# PowerSection.net
KiCad netlist of a schematic drawn in EAGLE
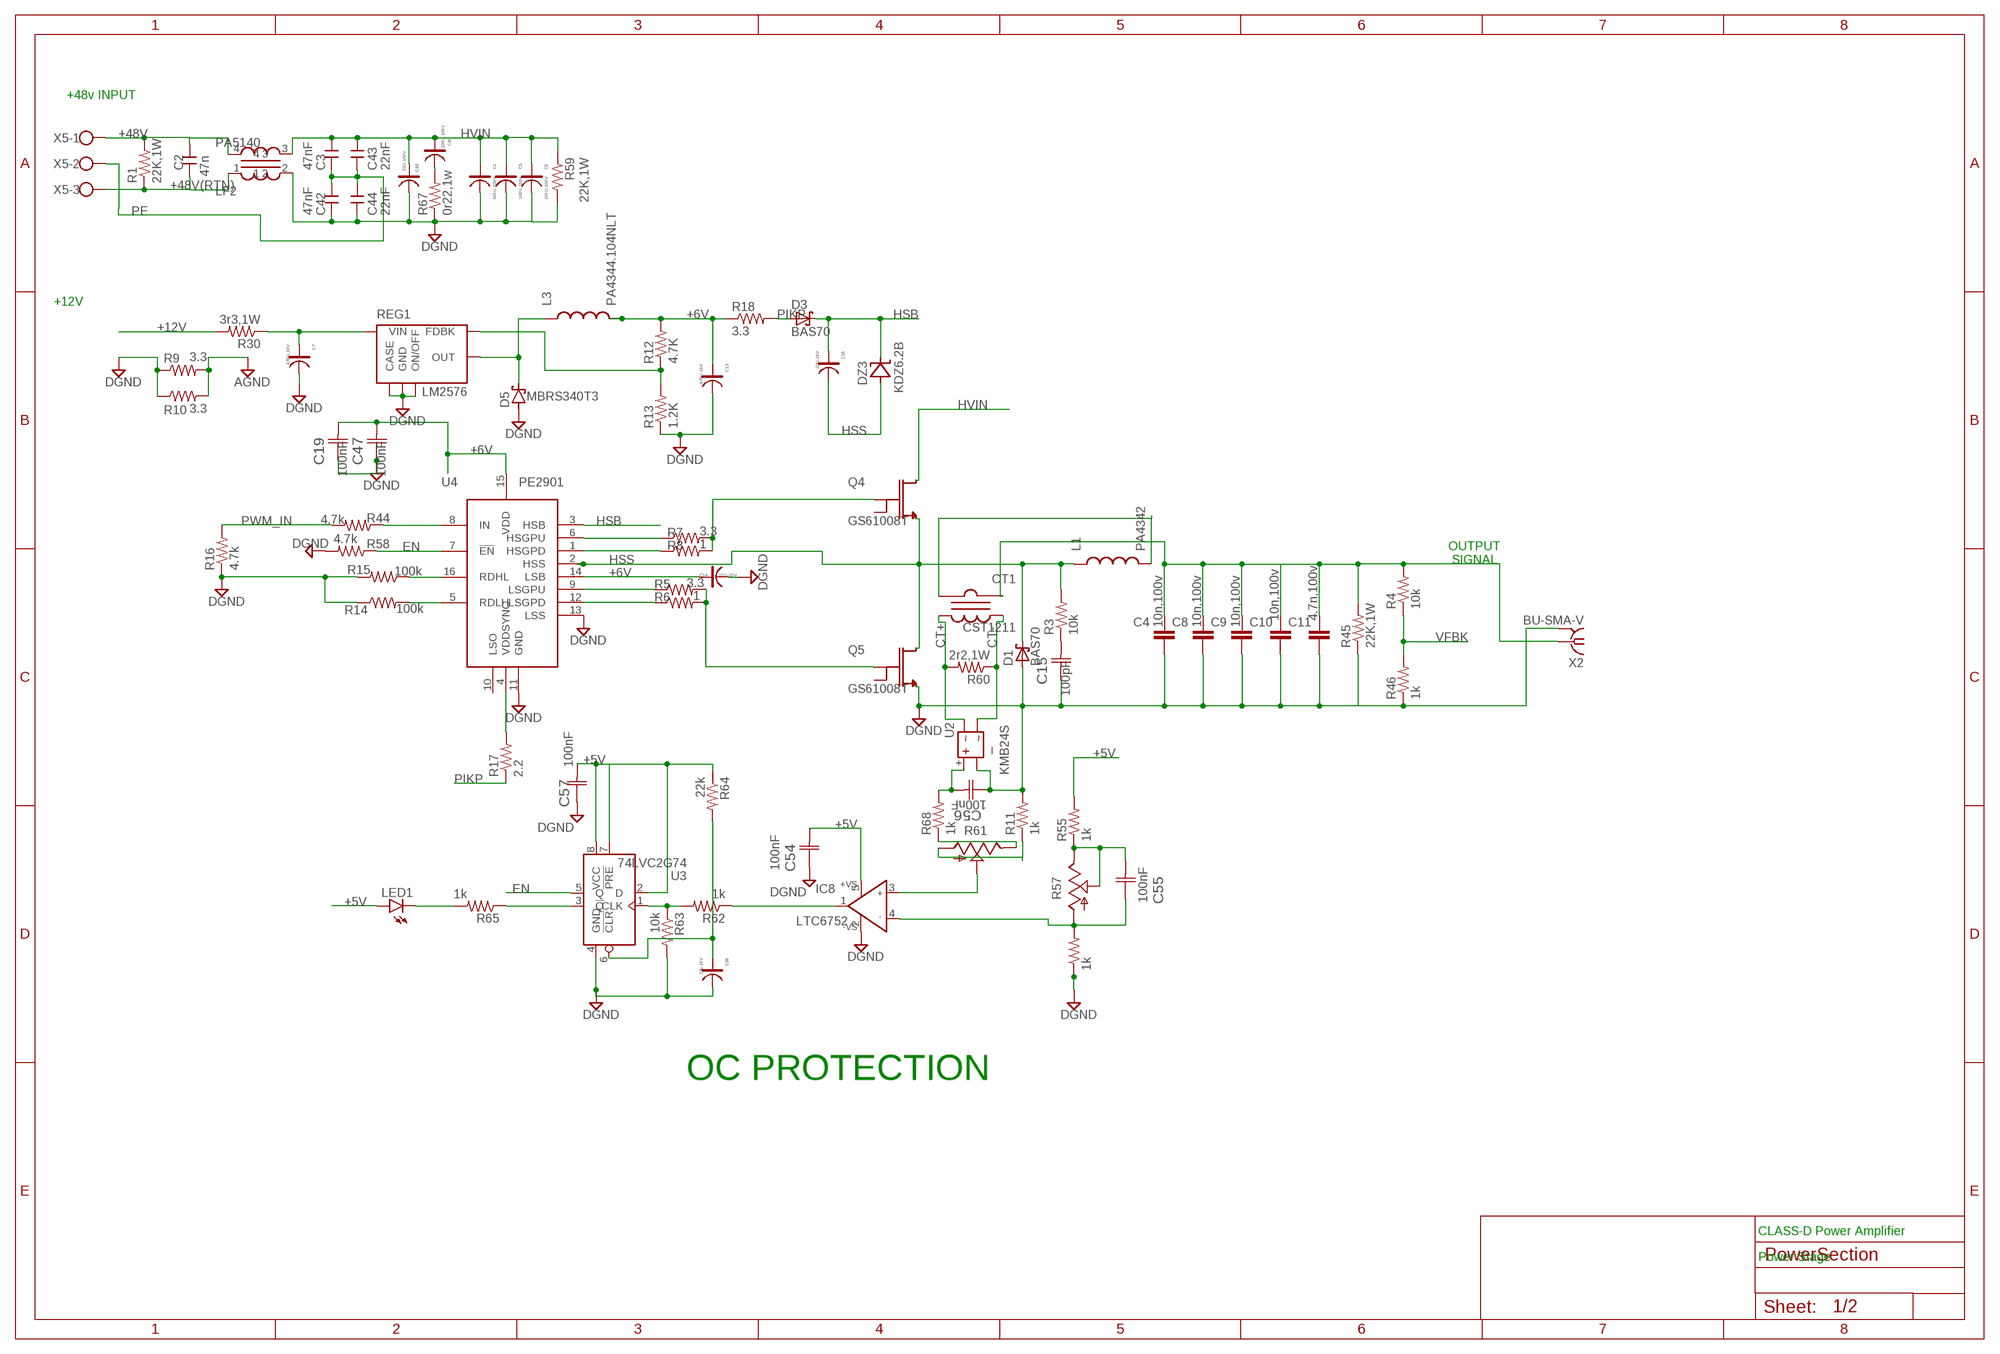
[diagram p0: schematic, sheet 1]
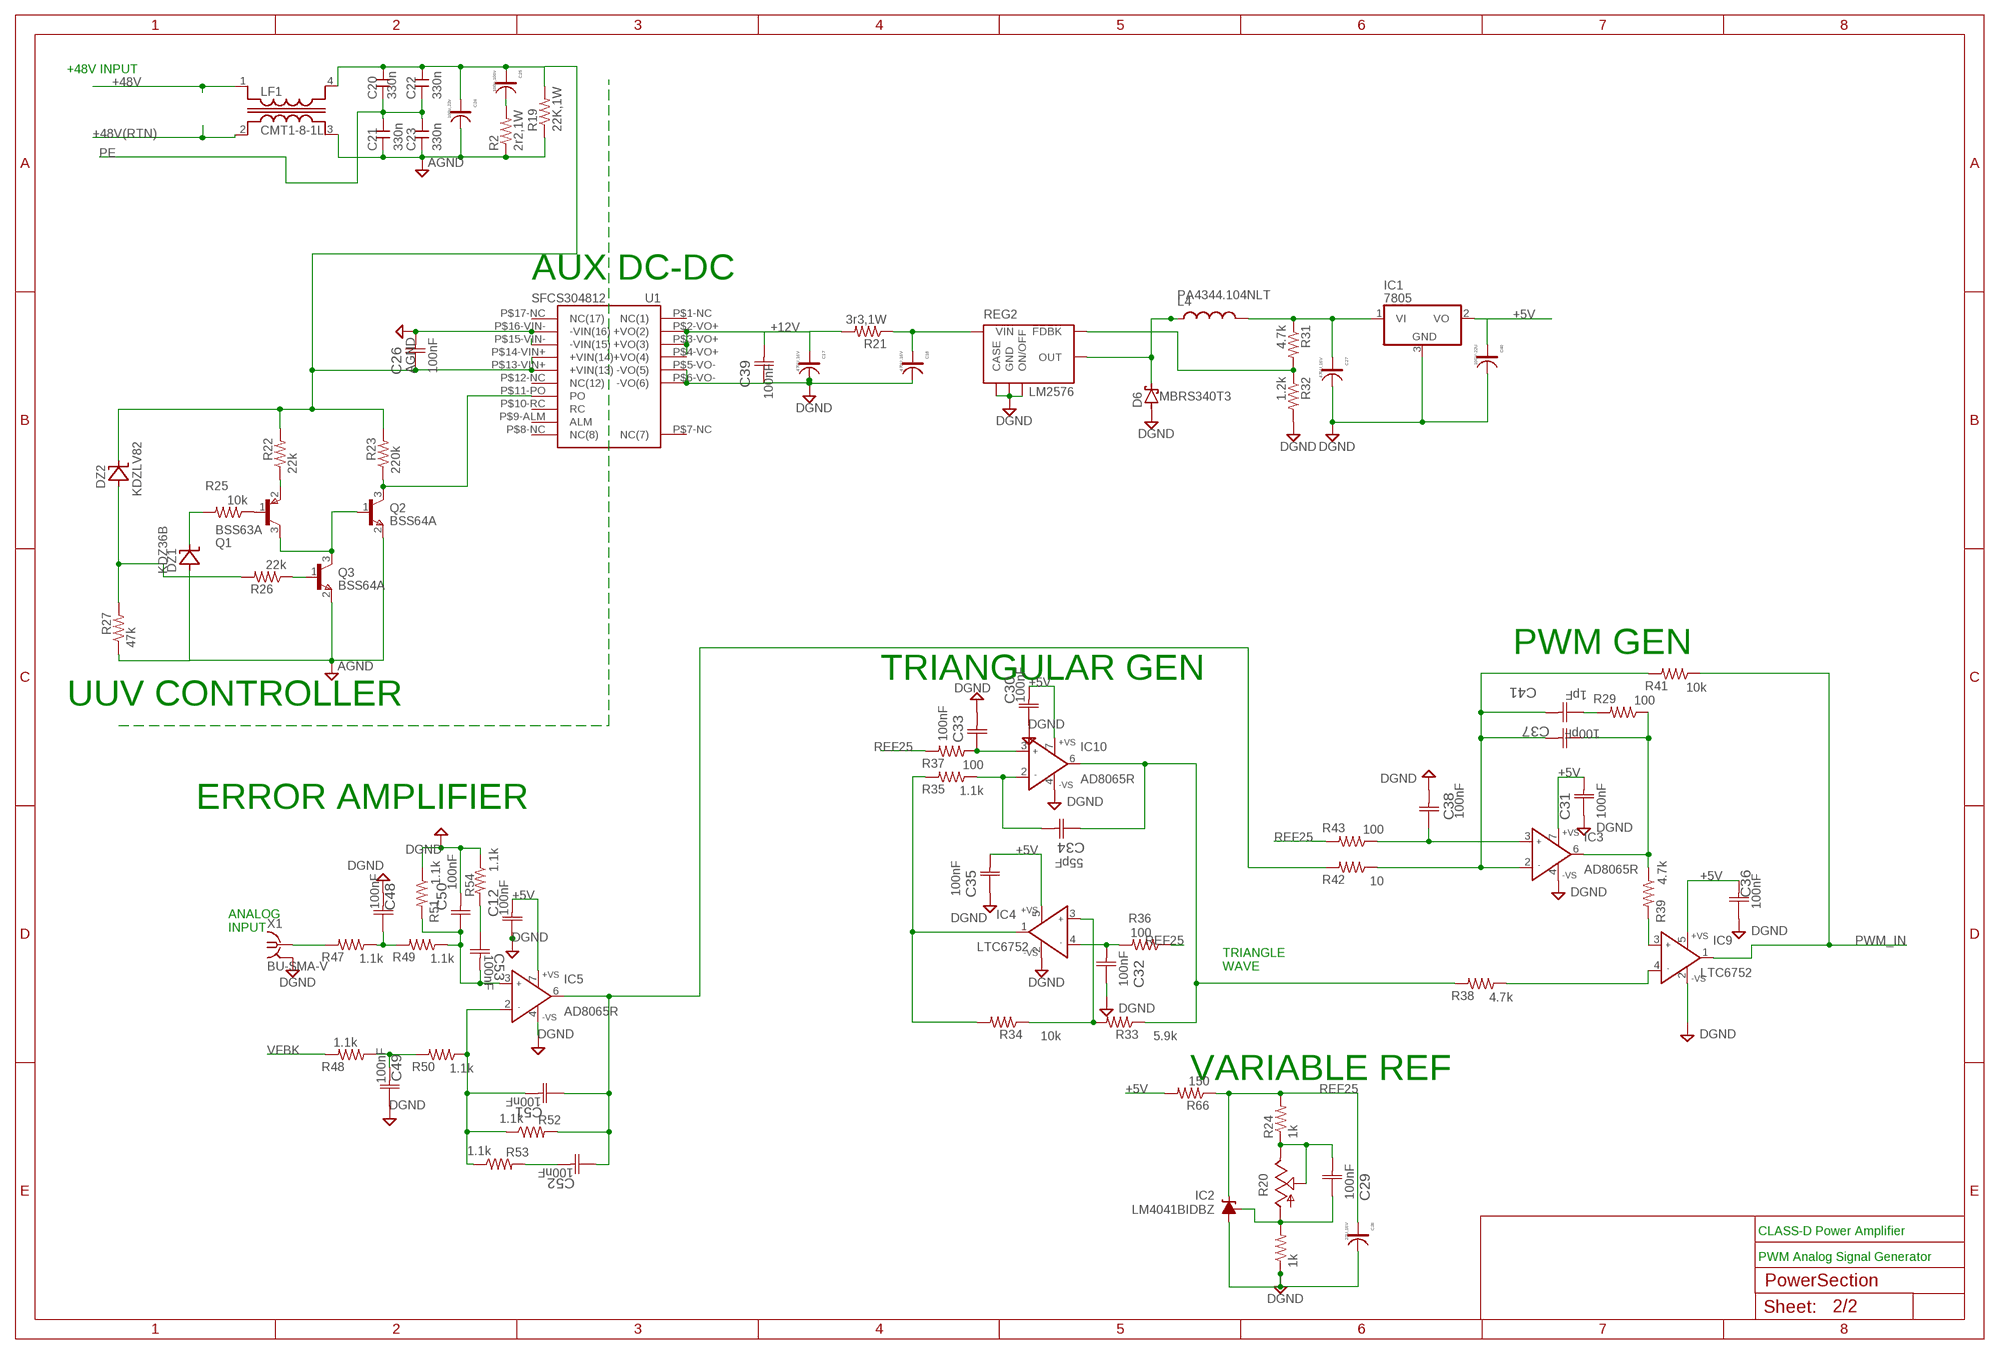
[diagram p1: schematic, sheet 2]

(export (version "E")
  (design (tool "Eeschema 10.0.6"))
  (components
    (comp (ref "C1")
      (value "100U,100V")
      (footprint "eagle-import:CEL-EDH-9R")
      (libsource (lib "eagle-import") (part "C-EDH-100V-100U"))
    )
    (comp (ref "C2")
      (value "47n")
      (footprint "eagle-import:2220")
      (libsource (lib "eagle-import") (part "C"))
    )
    (comp (ref "C3")
      (value "47nF")
      (footprint "eagle-import:2220")
      (libsource (lib "eagle-import") (part "C-SMD-2220"))
    )
    (comp (ref "C4")
      (value "10n,100v")
      (footprint "eagle-import:C2220K")
      (libsource (lib "eagle-import") (part "C-EUC2220K"))
    )
    (comp (ref "C5")
      (value "100U,100v")
      (footprint "eagle-import:CEL-EDH-9R")
      (libsource (lib "eagle-import") (part "C-EDH-100V-100U"))
    )
    (comp (ref "C6")
      (value "100U,100V")
      (footprint "eagle-import:CEL-EDH-9R")
      (libsource (lib "eagle-import") (part "C-EDH-100V-100U"))
    )
    (comp (ref "C7")
      (value "470U,16V")
      (footprint "eagle-import:CEL-EDH-9P")
      (libsource (lib "eagle-import") (part "C-EDH-470U,16V"))
    )
    (comp (ref "C8")
      (value "10n,100v")
      (footprint "eagle-import:C2220K")
      (libsource (lib "eagle-import") (part "C-EUC2220K"))
    )
    (comp (ref "C9")
      (value "10n,100v")
      (footprint "eagle-import:C2220K")
      (libsource (lib "eagle-import") (part "C-EUC2220K"))
    )
    (comp (ref "C10")
      (value "10n,100v")
      (footprint "eagle-import:C2220K")
      (libsource (lib "eagle-import") (part "C-EUC2220K"))
    )
    (comp (ref "C11")
      (value "4.7n,100v")
      (footprint "eagle-import:C2225K")
      (libsource (lib "eagle-import") (part "C-EUC2225K"))
    )
    (comp (ref "C13")
      (value "470U,16V")
      (footprint "eagle-import:CEL-EDH-9P")
      (libsource (lib "eagle-import") (part "C-EDH-470U,16V"))
    )
    (comp (ref "C14")
      (value "10U-16V")
      (footprint "eagle-import:CEL-EDK-9B")
      (libsource (lib "eagle-import") (part "C-EDK-10U-16V"))
    )
    (comp (ref "C15")
      (value "100pF")
      (footprint "eagle-import:CAPC3216X88N")
      (fields (field (name "MPN") "C1206C104K1RACTU") (field (name "TOLERANCE") "±10%"))
      (libsource (lib "eagle-import") (part "C1206C104K1RACTU"))
    )
    (comp (ref "C16")
      (value "22U,16V")
      (footprint "eagle-import:CEL-EDK-9D")
      (libsource (lib "eagle-import") (part "C-EDK-22U-16V"))
    )
    (comp (ref "C19")
      (value "100nF")
      (footprint "eagle-import:CAPC3216X88N")
      (fields (field (name "MPN") "C1206C104K1RACTU") (field (name "TOLERANCE") "±10%"))
      (libsource (lib "eagle-import") (part "C1206C104K1RACTU"))
    )
    (comp (ref "C42")
      (value "47nF")
      (footprint "eagle-import:2220")
      (libsource (lib "eagle-import") (part "C-SMD-2220"))
    )
    (comp (ref "C43")
      (value "22nF")
      (footprint "eagle-import:2220")
      (libsource (lib "eagle-import") (part "C-SMD-2220"))
    )
    (comp (ref "C44")
      (value "22nF")
      (footprint "eagle-import:2220")
      (libsource (lib "eagle-import") (part "C-SMD-2220"))
    )
    (comp (ref "C45")
      (value "22U,100V")
      (footprint "eagle-import:CEL-EDH-9M")
      (libsource (lib "eagle-import") (part "C-EDH-100V-22U"))
    )
    (comp (ref "C46")
      (value "100U,100V")
      (footprint "eagle-import:CEL-EDH-9R")
      (libsource (lib "eagle-import") (part "C-EDH-100V-100U"))
    )
    (comp (ref "C47")
      (value "100nF")
      (footprint "eagle-import:CAPC3216X88N")
      (fields (field (name "MPN") "C1206C104K1RACTU") (field (name "TOLERANCE") "±10%"))
      (libsource (lib "eagle-import") (part "C1206C104K1RACTU"))
    )
    (comp (ref "C54")
      (value "100nF")
      (footprint "eagle-import:CAPC3216X88N")
      (fields (field (name "MPN") "C1206C104K5RACTU") (field (name "TOLERANCE") "±10%"))
      (libsource (lib "eagle-import") (part "C1206C104K5RACTU"))
    )
    (comp (ref "C55")
      (value "100nF")
      (footprint "eagle-import:CAPC3216X88N")
      (fields (field (name "MPN") "C1206C104K5RACTU") (field (name "TOLERANCE") "±10%"))
      (libsource (lib "eagle-import") (part "C1206C104K5RACTU"))
    )
    (comp (ref "C56")
      (value "100nF")
      (footprint "eagle-import:CAPC3216X88N")
      (fields (field (name "MPN") "C1206C104K5RACTU") (field (name "TOLERANCE") "±10%"))
      (libsource (lib "eagle-import") (part "C1206C104K5RACTU"))
    )
    (comp (ref "C57")
      (value "100nF")
      (footprint "eagle-import:CAPC3216X88N")
      (fields (field (name "MPN") "C1206C104K5RACTU") (field (name "TOLERANCE") "±10%"))
      (libsource (lib "eagle-import") (part "C1206C104K5RACTU"))
    )
    (comp (ref "C58")
      (value "22u,16V")
      (footprint "eagle-import:CEL-EDK-9D")
      (libsource (lib "eagle-import") (part "C-EDK-22U-16V"))
    )
    (comp (ref "CT1")
      (value "CST1211")
      (footprint "eagle-import:CST1211")
      (libsource (lib "eagle-import") (part "CST1211"))
    )
    (comp (ref "D1")
      (value "BAS70")
      (footprint "eagle-import:SOT23")
      (libsource (lib "eagle-import") (part "BAS70"))
    )
    (comp (ref "D3")
      (value "BAS70")
      (footprint "eagle-import:SOT23")
      (libsource (lib "eagle-import") (part "BAS70"))
    )
    (comp (ref "D5")
      (value "MBRS340T3")
      (footprint "eagle-import:SMC")
      (libsource (lib "eagle-import") (part "MBRS30T34"))
    )
    (comp (ref "DZ3")
      (value "KDZ6.2B")
      (footprint "eagle-import:SOD123FL")
      (libsource (lib "eagle-import") (part "KDZ36B"))
    )
    (comp (ref "IC8")
      (value "LTC6752")
      (footprint "eagle-import:SOT23-5")
      (fields (field (name "MF") "ALTERA CORPORATION") (field (name "MPN") "AD8065ARTZ-REEL7"))
      (libsource (lib "eagle-import") (part "AD8065RT"))
    )
    (comp (ref "L1")
      (value "PA4342")
      (footprint "eagle-import:PA4342")
      (libsource (lib "eagle-import") (part "PA4342"))
    )
    (comp (ref "L3")
      (value "PA4344.104NLT")
      (footprint "eagle-import:104NLT")
      (libsource (lib "eagle-import") (part "PA4344.104NLT"))
    )
    (comp (ref "LED1")
      (value "LEDCHIPLED_1206")
      (footprint "eagle-import:CHIPLED_1206")
      (libsource (lib "eagle-import") (part "LEDCHIPLED_1206"))
    )
    (comp (ref "LF2")
      (value "PA5140")
      (footprint "eagle-import:PA5140.XXXNL")
      (libsource (lib "eagle-import") (part "PA5140"))
    )
    (comp (ref "Q4")
      (value "GS61008T")
      (footprint "eagle-import:61008T")
      (libsource (lib "eagle-import") (part "GS61008T"))
    )
    (comp (ref "Q5")
      (value "GS61008T")
      (footprint "eagle-import:61008T")
      (libsource (lib "eagle-import") (part "GS61008T"))
    )
    (comp (ref "R1")
      (value "22K,1W")
      (footprint "eagle-import:R2512W")
      (libsource (lib "eagle-import") (part "R-US_R2512W"))
    )
    (comp (ref "R3")
      (value "10k")
      (footprint "eagle-import:R1206")
      (libsource (lib "eagle-import") (part "R-US_R1206"))
    )
    (comp (ref "R4")
      (value "10k")
      (footprint "eagle-import:R1206")
      (libsource (lib "eagle-import") (part "R-US_R1206"))
    )
    (comp (ref "R5")
      (value "3.3")
      (footprint "eagle-import:R1206")
      (libsource (lib "eagle-import") (part "R-US_R1206"))
    )
    (comp (ref "R6")
      (value "1")
      (footprint "eagle-import:R1206")
      (libsource (lib "eagle-import") (part "R-US_R1206"))
    )
    (comp (ref "R7")
      (value "3.3")
      (footprint "eagle-import:R1206")
      (libsource (lib "eagle-import") (part "R-US_R1206"))
    )
    (comp (ref "R8")
      (value "1")
      (footprint "eagle-import:R1206")
      (libsource (lib "eagle-import") (part "R-US_R1206"))
    )
    (comp (ref "R9")
      (value "3.3")
      (footprint "eagle-import:R1206")
      (libsource (lib "eagle-import") (part "R-US_R1206"))
    )
    (comp (ref "R10")
      (value "3.3")
      (footprint "eagle-import:R1206")
      (libsource (lib "eagle-import") (part "R-US_R1206"))
    )
    (comp (ref "R11")
      (value "1k")
      (footprint "eagle-import:R1206")
      (libsource (lib "eagle-import") (part "R-US_R1206"))
    )
    (comp (ref "R12")
      (value "4.7K")
      (footprint "eagle-import:R1206")
      (libsource (lib "eagle-import") (part "R-US_R1206"))
    )
    (comp (ref "R13")
      (value "1.2K")
      (footprint "eagle-import:R1206")
      (libsource (lib "eagle-import") (part "R-US_R1206"))
    )
    (comp (ref "R14")
      (value "100k")
      (footprint "eagle-import:R1206")
      (libsource (lib "eagle-import") (part "R-US_R1206"))
    )
    (comp (ref "R15")
      (value "100k")
      (footprint "eagle-import:R1206")
      (libsource (lib "eagle-import") (part "R-US_R1206"))
    )
    (comp (ref "R16")
      (value "4.7k")
      (footprint "eagle-import:R1206")
      (libsource (lib "eagle-import") (part "R-US_R1206"))
    )
    (comp (ref "R17")
      (value "2.2")
      (footprint "eagle-import:R1206")
      (libsource (lib "eagle-import") (part "R-US_R1206"))
    )
    (comp (ref "R18")
      (value "3.3")
      (footprint "eagle-import:R1206")
      (libsource (lib "eagle-import") (part "R-US_R1206"))
    )
    (comp (ref "R30")
      (value "3r3,1W")
      (footprint "eagle-import:R2512W")
      (libsource (lib "eagle-import") (part "R-US_R2512W"))
    )
    (comp (ref "R44")
      (value "4.7k")
      (footprint "eagle-import:R1206")
      (libsource (lib "eagle-import") (part "R-US_R1206"))
    )
    (comp (ref "R45")
      (value "22K,1W")
      (footprint "eagle-import:R2512W")
      (libsource (lib "eagle-import") (part "R-US_R2512W"))
    )
    (comp (ref "R46")
      (value "1k")
      (footprint "eagle-import:R1206")
      (libsource (lib "eagle-import") (part "R-US_R1206"))
    )
    (comp (ref "R55")
      (value "1k")
      (footprint "eagle-import:R1206")
      (libsource (lib "eagle-import") (part "R-US_R1206"))
    )
    (comp (ref "R56")
      (value "1k")
      (footprint "eagle-import:R1206")
      (libsource (lib "eagle-import") (part "R-US_R1206"))
    )
    (comp (ref "R57")
      (value "TRIM_US-3223G")
      (footprint "eagle-import:3223G")
      (libsource (lib "eagle-import") (part "TRIM_US-3223G"))
    )
    (comp (ref "R58")
      (value "4.7k")
      (footprint "eagle-import:R1206")
      (libsource (lib "eagle-import") (part "R-US_R1206"))
    )
    (comp (ref "R59")
      (value "22K,1W")
      (footprint "eagle-import:R2512W")
      (libsource (lib "eagle-import") (part "R-US_R2512W"))
    )
    (comp (ref "R60")
      (value "2r2,1W")
      (footprint "eagle-import:R2512W")
      (libsource (lib "eagle-import") (part "R-US_R2512W"))
    )
    (comp (ref "R61")
      (value "TRIM_US-3223G")
      (footprint "eagle-import:3223G")
      (libsource (lib "eagle-import") (part "TRIM_US-3223G"))
    )
    (comp (ref "R62")
      (value "1k")
      (footprint "eagle-import:R1206")
      (libsource (lib "eagle-import") (part "R-US_R1206"))
    )
    (comp (ref "R63")
      (value "10k")
      (footprint "eagle-import:R1206")
      (libsource (lib "eagle-import") (part "R-US_R1206"))
    )
    (comp (ref "R64")
      (value "22k")
      (footprint "eagle-import:R1206")
      (libsource (lib "eagle-import") (part "R-US_R1206"))
    )
    (comp (ref "R65")
      (value "1k")
      (footprint "eagle-import:R1206")
      (libsource (lib "eagle-import") (part "R-US_R1206"))
    )
    (comp (ref "R67")
      (value "0r22,1w")
      (footprint "eagle-import:R2512W")
      (libsource (lib "eagle-import") (part "R-US_R2512W"))
    )
    (comp (ref "R68")
      (value "1k")
      (footprint "eagle-import:R1206")
      (libsource (lib "eagle-import") (part "R-US_R1206"))
    )
    (comp (ref "REG1")
      (value "LM2576")
      (footprint "eagle-import:TO263-5")
      (libsource (lib "eagle-import") (part "LM2576"))
    )
    (comp (ref "U2")
      (value "KMB24S")
      (footprint "eagle-import:SOIC-4")
      (libsource (lib "eagle-import") (part "KMB24S"))
    )
    (comp (ref "U3")
      (value "74LVC2G74")
      (footprint "eagle-import:SOT765")
      (libsource (lib "eagle-import") (part "74LVC2G74"))
    )
    (comp (ref "U4")
      (value "PE2901")
      (footprint "eagle-import:BGA20C40P5X4_164X204X28")
      (libsource (lib "eagle-import") (part "PE2901"))
    )
    (comp (ref "X2")
      (value "BU-SMA-V")
      (footprint "eagle-import:BU-SMA-V")
      (libsource (lib "eagle-import") (part "BU-SMA-V"))
    )
    (comp (ref "X5")
      (value "W237-103")
      (footprint "eagle-import:W237-103")
      (fields (field (name "MPN") "237-103"))
      (libsource (lib "eagle-import") (part "W237-103"))
    )
    (comp (ref "C12")
      (value "100nF")
      (footprint "eagle-import:CAPC3216X88N")
      (fields (field (name "MPN") "C1206C104K5RACTU") (field (name "TOLERANCE") "±10%"))
      (libsource (lib "eagle-import") (part "C1206C104K5RACTU"))
    )
    (comp (ref "C17")
      (value "470U,16V")
      (footprint "eagle-import:CEL-EDH-9P")
      (libsource (lib "eagle-import") (part "C-EDH-470U,16V"))
    )
    (comp (ref "C18")
      (value "470U,16V")
      (footprint "eagle-import:CEL-EDH-9P")
      (libsource (lib "eagle-import") (part "C-EDH-470U,16V"))
    )
    (comp (ref "C20")
      (value "330n")
      (footprint "eagle-import:2220")
      (libsource (lib "eagle-import") (part "C"))
    )
    (comp (ref "C21")
      (value "330n")
      (footprint "eagle-import:2220")
      (libsource (lib "eagle-import") (part "C"))
    )
    (comp (ref "C22")
      (value "330n")
      (footprint "eagle-import:2220")
      (libsource (lib "eagle-import") (part "C"))
    )
    (comp (ref "C23")
      (value "330n")
      (footprint "eagle-import:2220")
      (libsource (lib "eagle-import") (part "C"))
    )
    (comp (ref "C24")
      (value "100u,22v")
      (footprint "eagle-import:CEL-EDH-9M")
      (libsource (lib "eagle-import") (part "C-EDH-100V-22U"))
    )
    (comp (ref "C25")
      (value "100u,100v")
      (footprint "eagle-import:CEL-EDH-9R")
      (libsource (lib "eagle-import") (part "C-EDH-100V-100U"))
    )
    (comp (ref "C26")
      (value "100nF")
      (footprint "eagle-import:CAPC3216X88N")
      (fields (field (name "MPN") "C1206C104K1RACTU") (field (name "TOLERANCE") "±10%"))
      (libsource (lib "eagle-import") (part "C1206C104K1RACTU"))
    )
    (comp (ref "C27")
      (value "470U,16V")
      (footprint "eagle-import:CEL-EDH-9P")
      (libsource (lib "eagle-import") (part "C-EDH-470U,16V"))
    )
    (comp (ref "C28")
      (value "22U,16V")
      (footprint "eagle-import:CEL-EDK-9D")
      (libsource (lib "eagle-import") (part "C-EDK-22U-16V"))
    )
    (comp (ref "C29")
      (value "100nF")
      (footprint "eagle-import:CAPC3216X88N")
      (fields (field (name "MPN") "C1206C104K5RACTU") (field (name "TOLERANCE") "±10%"))
      (libsource (lib "eagle-import") (part "C1206C104K5RACTU"))
    )
    (comp (ref "C30")
      (value "100nF")
      (footprint "eagle-import:CAPC3216X88N")
      (fields (field (name "MPN") "C1206C104K5RACTU") (field (name "TOLERANCE") "±10%"))
      (libsource (lib "eagle-import") (part "C1206C104K5RACTU"))
    )
    (comp (ref "C31")
      (value "100nF")
      (footprint "eagle-import:CAPC3216X88N")
      (fields (field (name "MPN") "C1206C104K5RACTU") (field (name "TOLERANCE") "±10%"))
      (libsource (lib "eagle-import") (part "C1206C104K5RACTU"))
    )
    (comp (ref "C32")
      (value "100nF")
      (footprint "eagle-import:CAPC3216X88N")
      (fields (field (name "MPN") "C1206C104K5RACTU") (field (name "TOLERANCE") "±10%"))
      (libsource (lib "eagle-import") (part "C1206C104K5RACTU"))
    )
    (comp (ref "C33")
      (value "100nF")
      (footprint "eagle-import:CAPC3216X88N")
      (fields (field (name "MPN") "C1206C104K5RACTU") (field (name "TOLERANCE") "±10%"))
      (libsource (lib "eagle-import") (part "C1206C104K5RACTU"))
    )
    (comp (ref "C34")
      (value "55pF")
      (footprint "eagle-import:CAPC3216X88N")
      (fields (field (name "MPN") "C1206C104K5RACTU") (field (name "TOLERANCE") "±10%"))
      (libsource (lib "eagle-import") (part "C1206C104K5RACTU"))
    )
    (comp (ref "C35")
      (value "100nF")
      (footprint "eagle-import:CAPC3216X88N")
      (fields (field (name "MPN") "C1206C104K5RACTU") (field (name "TOLERANCE") "±10%"))
      (libsource (lib "eagle-import") (part "C1206C104K5RACTU"))
    )
    (comp (ref "C36")
      (value "100nF")
      (footprint "eagle-import:CAPC3216X88N")
      (fields (field (name "MPN") "C1206C104K5RACTU") (field (name "TOLERANCE") "±10%"))
      (libsource (lib "eagle-import") (part "C1206C104K5RACTU"))
    )
    (comp (ref "C37")
      (value "100pF")
      (footprint "eagle-import:CAPC3216X88N")
      (fields (field (name "MPN") "C1206C104K5RACTU") (field (name "TOLERANCE") "±10%"))
      (libsource (lib "eagle-import") (part "C1206C104K5RACTU"))
    )
    (comp (ref "C38")
      (value "100nF")
      (footprint "eagle-import:CAPC3216X88N")
      (fields (field (name "MPN") "C1206C104K5RACTU") (field (name "TOLERANCE") "±10%"))
      (libsource (lib "eagle-import") (part "C1206C104K5RACTU"))
    )
    (comp (ref "C39")
      (value "100nF")
      (footprint "eagle-import:CAPC3216X88N")
      (fields (field (name "MPN") "C1206C104K1RACTU") (field (name "TOLERANCE") "±10%"))
      (libsource (lib "eagle-import") (part "C1206C104K1RACTU"))
    )
    (comp (ref "C40")
      (value "100V-22U")
      (footprint "eagle-import:CEL-EDH-9M")
      (libsource (lib "eagle-import") (part "C-EDH-100V-22U"))
    )
    (comp (ref "C41")
      (value "1pF")
      (footprint "eagle-import:CAPC3216X88N")
      (fields (field (name "MPN") "C1206C104K5RACTU") (field (name "TOLERANCE") "±10%"))
      (libsource (lib "eagle-import") (part "C1206C104K5RACTU"))
    )
    (comp (ref "C48")
      (value "100nF")
      (footprint "eagle-import:CAPC3216X88N")
      (fields (field (name "MPN") "C1206C104K5RACTU") (field (name "TOLERANCE") "±10%"))
      (libsource (lib "eagle-import") (part "C1206C104K5RACTU"))
    )
    (comp (ref "C49")
      (value "100nF")
      (footprint "eagle-import:CAPC3216X88N")
      (fields (field (name "MPN") "C1206C104K5RACTU") (field (name "TOLERANCE") "±10%"))
      (libsource (lib "eagle-import") (part "C1206C104K5RACTU"))
    )
    (comp (ref "C50")
      (value "100nF")
      (footprint "eagle-import:CAPC3216X88N")
      (fields (field (name "MPN") "C1206C104K5RACTU") (field (name "TOLERANCE") "±10%"))
      (libsource (lib "eagle-import") (part "C1206C104K5RACTU"))
    )
    (comp (ref "C51")
      (value "100nF")
      (footprint "eagle-import:CAPC3216X88N")
      (fields (field (name "MPN") "C1206C104K5RACTU") (field (name "TOLERANCE") "±10%"))
      (libsource (lib "eagle-import") (part "C1206C104K5RACTU"))
    )
    (comp (ref "C52")
      (value "100nF")
      (footprint "eagle-import:CAPC3216X88N")
      (fields (field (name "MPN") "C1206C104K5RACTU") (field (name "TOLERANCE") "±10%"))
      (libsource (lib "eagle-import") (part "C1206C104K5RACTU"))
    )
    (comp (ref "C53")
      (value "100nF")
      (footprint "eagle-import:CAPC3216X88N")
      (fields (field (name "MPN") "C1206C104K5RACTU") (field (name "TOLERANCE") "±10%"))
      (libsource (lib "eagle-import") (part "C1206C104K5RACTU"))
    )
    (comp (ref "D6")
      (value "MBRS340T3")
      (footprint "eagle-import:SMC")
      (libsource (lib "eagle-import") (part "MBRS30T34"))
    )
    (comp (ref "DZ1")
      (value "KDZ36B")
      (footprint "eagle-import:SOD123FL")
      (libsource (lib "eagle-import") (part "KDZ36B"))
    )
    (comp (ref "DZ2")
      (value "KDZLV82")
      (footprint "eagle-import:SOD123FL")
      (libsource (lib "eagle-import") (part "KDZLV82"))
    )
    (comp (ref "IC1")
      (value "7805")
      (footprint "eagle-import:TO252")
      (libsource (lib "eagle-import") (part "78DT15"))
    )
    (comp (ref "IC2")
      (value "LM4041BIDBZ")
      (footprint "eagle-import:DBZ_R-PDSO-G3")
      (libsource (lib "eagle-import") (part "LM4041IDBZB"))
    )
    (comp (ref "IC3")
      (value "AD8065R")
      (footprint "eagle-import:SO8")
      (libsource (lib "eagle-import") (part "AD8065R"))
    )
    (comp (ref "IC4")
      (value "LTC6752")
      (footprint "eagle-import:SOT23-5")
      (fields (field (name "MF") "ALTERA CORPORATION") (field (name "MPN") "AD8065ARTZ-REEL7"))
      (libsource (lib "eagle-import") (part "AD8065RT"))
    )
    (comp (ref "IC5")
      (value "AD8065R")
      (footprint "eagle-import:SO8")
      (libsource (lib "eagle-import") (part "AD8065R"))
    )
    (comp (ref "IC9")
      (value "LTC6752")
      (footprint "eagle-import:SOT23-5")
      (fields (field (name "MF") "ALTERA CORPORATION") (field (name "MPN") "AD8065ARTZ-REEL7"))
      (libsource (lib "eagle-import") (part "AD8065RT"))
    )
    (comp (ref "IC10")
      (value "AD8065R")
      (footprint "eagle-import:SO8")
      (libsource (lib "eagle-import") (part "AD8065R"))
    )
    (comp (ref "L4")
      (value "PA4344.104NLT")
      (footprint "eagle-import:104NLT")
      (libsource (lib "eagle-import") (part "PA4344.104NLT"))
    )
    (comp (ref "LF1")
      (value "CMT1-8-1L")
      (footprint "eagle-import:CMT1-8-1L")
      (libsource (lib "eagle-import") (part "CMT1-8-1L"))
    )
    (comp (ref "Q1")
      (value "BSS63A")
      (footprint "eagle-import:SOT23")
      (libsource (lib "eagle-import") (part "BSS63A"))
    )
    (comp (ref "Q2")
      (value "BSS64A")
      (footprint "eagle-import:SOT23")
      (libsource (lib "eagle-import") (part "BSS64A"))
    )
    (comp (ref "Q3")
      (value "BSS64A")
      (footprint "eagle-import:SOT23")
      (libsource (lib "eagle-import") (part "BSS64A"))
    )
    (comp (ref "R2")
      (value "2r2,1W")
      (footprint "eagle-import:R2512W")
      (libsource (lib "eagle-import") (part "R-US_R2512W"))
    )
    (comp (ref "R19")
      (value "22K,1W")
      (footprint "eagle-import:R2512W")
      (libsource (lib "eagle-import") (part "R-US_R2512W"))
    )
    (comp (ref "R20")
      (value "TRIM_US-3223G")
      (footprint "eagle-import:3223G")
      (libsource (lib "eagle-import") (part "TRIM_US-3223G"))
    )
    (comp (ref "R21")
      (value "3r3,1W")
      (footprint "eagle-import:R2512W")
      (libsource (lib "eagle-import") (part "R-US_R2512W"))
    )
    (comp (ref "R22")
      (value "22k")
      (footprint "eagle-import:R1206")
      (libsource (lib "eagle-import") (part "R-US_R1206"))
    )
    (comp (ref "R23")
      (value "220k")
      (footprint "eagle-import:R1206")
      (libsource (lib "eagle-import") (part "R-US_R1206"))
    )
    (comp (ref "R24")
      (value "1k")
      (footprint "eagle-import:R1206")
      (libsource (lib "eagle-import") (part "R-US_R1206"))
    )
    (comp (ref "R25")
      (value "10k")
      (footprint "eagle-import:R1206")
      (libsource (lib "eagle-import") (part "R-US_R1206"))
    )
    (comp (ref "R26")
      (value "22k")
      (footprint "eagle-import:R1206")
      (libsource (lib "eagle-import") (part "R-US_R1206"))
    )
    (comp (ref "R27")
      (value "47k")
      (footprint "eagle-import:R1206")
      (libsource (lib "eagle-import") (part "R-US_R1206"))
    )
    (comp (ref "R28")
      (value "1k")
      (footprint "eagle-import:R1206")
      (libsource (lib "eagle-import") (part "R-US_R1206"))
    )
    (comp (ref "R29")
      (value "100")
      (footprint "eagle-import:R1206")
      (libsource (lib "eagle-import") (part "R-US_R1206"))
    )
    (comp (ref "R31")
      (value "4.7k")
      (footprint "eagle-import:R1206")
      (libsource (lib "eagle-import") (part "R-US_R1206"))
    )
    (comp (ref "R32")
      (value "1.2k")
      (footprint "eagle-import:R1206")
      (libsource (lib "eagle-import") (part "R-US_R1206"))
    )
    (comp (ref "R33")
      (value "5.9k")
      (footprint "eagle-import:R1206")
      (libsource (lib "eagle-import") (part "R-US_R1206"))
    )
    (comp (ref "R34")
      (value "10k")
      (footprint "eagle-import:R1206")
      (libsource (lib "eagle-import") (part "R-US_R1206"))
    )
    (comp (ref "R35")
      (value "1.1k")
      (footprint "eagle-import:R1206")
      (libsource (lib "eagle-import") (part "R-US_R1206"))
    )
    (comp (ref "R36")
      (value "100")
      (footprint "eagle-import:R1206")
      (libsource (lib "eagle-import") (part "R-US_R1206"))
    )
    (comp (ref "R37")
      (value "100")
      (footprint "eagle-import:R1206")
      (libsource (lib "eagle-import") (part "R-US_R1206"))
    )
    (comp (ref "R38")
      (value "4.7k")
      (footprint "eagle-import:R1206")
      (libsource (lib "eagle-import") (part "R-US_R1206"))
    )
    (comp (ref "R39")
      (value "4.7k")
      (footprint "eagle-import:R1206")
      (libsource (lib "eagle-import") (part "R-US_R1206"))
    )
    (comp (ref "R41")
      (value "10k")
      (footprint "eagle-import:R1206")
      (libsource (lib "eagle-import") (part "R-US_R1206"))
    )
    (comp (ref "R42")
      (value "10")
      (footprint "eagle-import:R1206")
      (libsource (lib "eagle-import") (part "R-US_R1206"))
    )
    (comp (ref "R43")
      (value "100")
      (footprint "eagle-import:R1206")
      (libsource (lib "eagle-import") (part "R-US_R1206"))
    )
    (comp (ref "R47")
      (value "1.1k")
      (footprint "eagle-import:R1206")
      (libsource (lib "eagle-import") (part "R-US_R1206"))
    )
    (comp (ref "R48")
      (value "1.1k")
      (footprint "eagle-import:R1206")
      (libsource (lib "eagle-import") (part "R-US_R1206"))
    )
    (comp (ref "R49")
      (value "1.1k")
      (footprint "eagle-import:R1206")
      (libsource (lib "eagle-import") (part "R-US_R1206"))
    )
    (comp (ref "R50")
      (value "1.1k")
      (footprint "eagle-import:R1206")
      (libsource (lib "eagle-import") (part "R-US_R1206"))
    )
    (comp (ref "R51")
      (value "1.1k")
      (footprint "eagle-import:R1206")
      (libsource (lib "eagle-import") (part "R-US_R1206"))
    )
    (comp (ref "R52")
      (value "1.1k")
      (footprint "eagle-import:R1206")
      (libsource (lib "eagle-import") (part "R-US_R1206"))
    )
    (comp (ref "R53")
      (value "1.1k")
      (footprint "eagle-import:R1206")
      (libsource (lib "eagle-import") (part "R-US_R1206"))
    )
    (comp (ref "R54")
      (value "1.1k")
      (footprint "eagle-import:R1206")
      (libsource (lib "eagle-import") (part "R-US_R1206"))
    )
    (comp (ref "R66")
      (value "150")
      (footprint "eagle-import:R1206")
      (libsource (lib "eagle-import") (part "R-US_R1206"))
    )
    (comp (ref "REG2")
      (value "LM2576")
      (footprint "eagle-import:TO263-5")
      (libsource (lib "eagle-import") (part "LM2576"))
    )
    (comp (ref "U1")
      (value "SFCS304812")
      (footprint "eagle-import:SFCS_SMD")
      (libsource (lib "eagle-import") (part "SFCS304812"))
    )
    (comp (ref "X1")
      (value "BU-SMA-V")
      (footprint "eagle-import:BU-SMA-V")
      (libsource (lib "eagle-import") (part "BU-SMA-V"))
    )
  )
  (nets
    (net (code "1") (name "+5V") (class "Default")
      (node (ref "C12") (pin "2") (pinfunction "C2_2") (pintype "passive"))
      (node (ref "C30") (pin "2") (pinfunction "C2_2") (pintype "passive"))
      (node (ref "C31") (pin "2") (pinfunction "C2_2") (pintype "passive"))
      (node (ref "C35") (pin "2") (pinfunction "C2_2") (pintype "passive"))
      (node (ref "C36") (pin "2") (pinfunction "C2_2") (pintype "passive"))
      (node (ref "C40") (pin "1") (pinfunction "1_1") (pintype "bidirectional"))
      (node (ref "C54") (pin "2") (pinfunction "C2_2") (pintype "passive"))
      (node (ref "C57") (pin "2") (pinfunction "C2_2") (pintype "passive"))
      (node (ref "IC1") (pin "2") (pinfunction "VO_2") (pintype "passive"))
      (node (ref "IC10") (pin "7") (pinfunction "+VS_7") (pintype "input"))
      (node (ref "IC3") (pin "7") (pinfunction "+VS_7") (pintype "input"))
      (node (ref "IC4") (pin "5") (pinfunction "+VS_5") (pintype "input"))
      (node (ref "IC5") (pin "7") (pinfunction "+VS_7") (pintype "input"))
      (node (ref "IC8") (pin "5") (pinfunction "+VS_5") (pintype "input"))
      (node (ref "IC9") (pin "5") (pinfunction "+VS_5") (pintype "input"))
      (node (ref "LED1") (pin "A") (pinfunction "A_A") (pintype "passive"))
      (node (ref "R55") (pin "2") (pinfunction "2_2") (pintype "passive"))
      (node (ref "R64") (pin "1") (pinfunction "1_1") (pintype "passive"))
      (node (ref "R66") (pin "2") (pinfunction "2_2") (pintype "passive"))
      (node (ref "U3") (pin "2") (pinfunction "D_2") (pintype "bidirectional"))
      (node (ref "U3") (pin "7") (pinfunction "~{PRE}_7") (pintype "bidirectional"))
      (node (ref "U3") (pin "8") (pinfunction "VCC_8") (pintype "bidirectional"))
    )
    (net (code "2") (name "+6V") (class "Default")
      (node (ref "C13") (pin "1") (pinfunction "1_1") (pintype "bidirectional"))
      (node (ref "C14") (pin "1") (pinfunction "1_1") (pintype "bidirectional"))
      (node (ref "C19") (pin "2") (pinfunction "C2_2") (pintype "passive"))
      (node (ref "C47") (pin "2") (pinfunction "C2_2") (pintype "passive"))
      (node (ref "L3") (pin "2") (pinfunction "2_2") (pintype "passive"))
      (node (ref "R12") (pin "2") (pinfunction "2_2") (pintype "passive"))
      (node (ref "R18") (pin "1") (pinfunction "1_1") (pintype "passive"))
      (node (ref "U4") (pin "14") (pinfunction "LSB_14") (pintype "bidirectional"))
      (node (ref "U4") (pin "15") (pinfunction "VDD_15") (pintype "bidirectional"))
    )
    (net (code "3") (name "+12V") (class "Default")
      (node (ref "C17") (pin "1") (pinfunction "1_1") (pintype "bidirectional"))
      (node (ref "C39") (pin "2") (pinfunction "C2_2") (pintype "passive"))
      (node (ref "R21") (pin "2") (pinfunction "2_2") (pintype "passive"))
      (node (ref "R30") (pin "2") (pinfunction "2_2") (pintype "passive"))
      (node (ref "U1") (pin "P$2-VO+") (pinfunction "+VO(2)_P$2-VO+") (pintype "bidirectional"))
      (node (ref "U1") (pin "P$3-VO+") (pinfunction "+VO(3)_P$3-VO+") (pintype "bidirectional"))
      (node (ref "U1") (pin "P$4-VO+") (pinfunction "+VO(4)_P$4-VO+") (pintype "bidirectional"))
    )
    (net (code "4") (name "+48V") (class "Default")
      (node (ref "C2") (pin "2") (pinfunction "2_2") (pintype "bidirectional"))
      (node (ref "LF1") (pin "1") (pinfunction "1_1") (pintype "bidirectional"))
      (node (ref "LF2") (pin "4") (pinfunction "4_4") (pintype "bidirectional"))
      (node (ref "R1") (pin "2") (pinfunction "2_2") (pintype "passive"))
      (node (ref "X5") (pin "1") (pinfunction "KL_1") (pintype "passive"))
    )
    (net (code "5") (name "+48V(RTN)") (class "Default")
      (node (ref "C2") (pin "1") (pinfunction "1_1") (pintype "bidirectional"))
      (node (ref "LF1") (pin "2") (pinfunction "2_2") (pintype "bidirectional"))
      (node (ref "LF2") (pin "1") (pinfunction "1_1") (pintype "bidirectional"))
      (node (ref "R1") (pin "1") (pinfunction "1_1") (pintype "passive"))
      (node (ref "X5") (pin "3") (pinfunction "KL_3") (pintype "passive"))
    )
    (net (code "6") (name "AGND") (class "Default")
      (node (ref "C21") (pin "1") (pinfunction "1_1") (pintype "bidirectional"))
      (node (ref "C23") (pin "1") (pinfunction "1_1") (pintype "bidirectional"))
      (node (ref "C24") (pin "2") (pinfunction "2_2") (pintype "bidirectional"))
      (node (ref "C26") (pin "2") (pinfunction "C2_2") (pintype "passive"))
      (node (ref "DZ1") (pin "A") (pinfunction "A_A") (pintype "passive"))
      (node (ref "LF1") (pin "3") (pinfunction "3_3") (pintype "bidirectional"))
      (node (ref "Q2") (pin "2") (pinfunction "E_2") (pintype "passive"))
      (node (ref "Q3") (pin "2") (pinfunction "E_2") (pintype "passive"))
      (node (ref "R10") (pin "2") (pinfunction "2_2") (pintype "passive"))
      (node (ref "R19") (pin "1") (pinfunction "1_1") (pintype "passive"))
      (node (ref "R2") (pin "1") (pinfunction "1_1") (pintype "passive"))
      (node (ref "R27") (pin "1") (pinfunction "1_1") (pintype "passive"))
      (node (ref "R9") (pin "2") (pinfunction "2_2") (pintype "passive"))
      (node (ref "U1") (pin "P$16-VIN-") (pinfunction "-VIN(16)_P$16-VIN-") (pintype "bidirectional"))
    )
    (net (code "7") (name "CT+") (class "Default")
      (node (ref "CT1") (pin "4") (pinfunction "V_-_4") (pintype "bidirectional"))
      (node (ref "R60") (pin "2") (pinfunction "2_2") (pintype "passive"))
      (node (ref "U2") (pin "~2") (pinfunction "2_~2") (pintype "bidirectional"))
    )
    (net (code "8") (name "CT-") (class "Default")
      (node (ref "CT1") (pin "5") (pinfunction "V_+_5") (pintype "bidirectional"))
      (node (ref "R60") (pin "1") (pinfunction "1_1") (pintype "passive"))
      (node (ref "U2") (pin "~1") (pinfunction "1_~1") (pintype "bidirectional"))
    )
    (net (code "9") (name "DGND") (class "Default")
      (node (ref "C1") (pin "2") (pinfunction "2_2") (pintype "bidirectional"))
      (node (ref "C10") (pin "2") (pinfunction "2_2") (pintype "passive"))
      (node (ref "C11") (pin "2") (pinfunction "2_2") (pintype "passive"))
      (node (ref "C12") (pin "1") (pinfunction "C1_1") (pintype "passive"))
      (node (ref "C13") (pin "2") (pinfunction "2_2") (pintype "bidirectional"))
      (node (ref "C14") (pin "2") (pinfunction "2_2") (pintype "bidirectional"))
      (node (ref "C15") (pin "1") (pinfunction "C1_1") (pintype "passive"))
      (node (ref "C17") (pin "2") (pinfunction "2_2") (pintype "bidirectional"))
      (node (ref "C18") (pin "2") (pinfunction "2_2") (pintype "bidirectional"))
      (node (ref "C19") (pin "1") (pinfunction "C1_1") (pintype "passive"))
      (node (ref "C27") (pin "2") (pinfunction "2_2") (pintype "bidirectional"))
      (node (ref "C28") (pin "2") (pinfunction "2_2") (pintype "bidirectional"))
      (node (ref "C30") (pin "1") (pinfunction "C1_1") (pintype "passive"))
      (node (ref "C31") (pin "1") (pinfunction "C1_1") (pintype "passive"))
      (node (ref "C32") (pin "1") (pinfunction "C1_1") (pintype "passive"))
      (node (ref "C33") (pin "2") (pinfunction "C2_2") (pintype "passive"))
      (node (ref "C35") (pin "1") (pinfunction "C1_1") (pintype "passive"))
      (node (ref "C36") (pin "1") (pinfunction "C1_1") (pintype "passive"))
      (node (ref "C38") (pin "2") (pinfunction "C2_2") (pintype "passive"))
      (node (ref "C39") (pin "1") (pinfunction "C1_1") (pintype "passive"))
      (node (ref "C4") (pin "2") (pinfunction "2_2") (pintype "passive"))
      (node (ref "C40") (pin "2") (pinfunction "2_2") (pintype "bidirectional"))
      (node (ref "C42") (pin "1") (pinfunction "1_1") (pintype "bidirectional"))
      (node (ref "C44") (pin "1") (pinfunction "1_1") (pintype "bidirectional"))
      (node (ref "C45") (pin "2") (pinfunction "2_2") (pintype "bidirectional"))
      (node (ref "C47") (pin "1") (pinfunction "C1_1") (pintype "passive"))
      (node (ref "C48") (pin "2") (pinfunction "C2_2") (pintype "passive"))
      (node (ref "C49") (pin "1") (pinfunction "C1_1") (pintype "passive"))
      (node (ref "C5") (pin "2") (pinfunction "2_2") (pintype "bidirectional"))
      (node (ref "C50") (pin "2") (pinfunction "C2_2") (pintype "passive"))
      (node (ref "C54") (pin "1") (pinfunction "C1_1") (pintype "passive"))
      (node (ref "C56") (pin "1") (pinfunction "C1_1") (pintype "passive"))
      (node (ref "C57") (pin "1") (pinfunction "C1_1") (pintype "passive"))
      (node (ref "C58") (pin "2") (pinfunction "2_2") (pintype "bidirectional"))
      (node (ref "C6") (pin "2") (pinfunction "2_2") (pintype "bidirectional"))
      (node (ref "C7") (pin "2") (pinfunction "2_2") (pintype "bidirectional"))
      (node (ref "C8") (pin "2") (pinfunction "2_2") (pintype "passive"))
      (node (ref "C9") (pin "2") (pinfunction "2_2") (pintype "passive"))
      (node (ref "D1") (pin "1") (pinfunction "A_1") (pintype "passive"))
      (node (ref "D5") (pin "A") (pinfunction "A_A") (pintype "passive"))
      (node (ref "D6") (pin "A") (pinfunction "A_A") (pintype "passive"))
      (node (ref "IC1") (pin "3") (pinfunction "GND_3") (pintype "passive"))
      (node (ref "IC10") (pin "4") (pinfunction "-VS_4") (pintype "input"))
      (node (ref "IC2") (pin "3") (pinfunction "A_3") (pintype "passive"))
      (node (ref "IC3") (pin "4") (pinfunction "-VS_4") (pintype "input"))
      (node (ref "IC4") (pin "2") (pinfunction "-VS_2") (pintype "input"))
      (node (ref "IC5") (pin "4") (pinfunction "-VS_4") (pintype "input"))
      (node (ref "IC8") (pin "2") (pinfunction "-VS_2") (pintype "input"))
      (node (ref "IC9") (pin "2") (pinfunction "-VS_2") (pintype "input"))
      (node (ref "LF2") (pin "2") (pinfunction "2_2") (pintype "bidirectional"))
      (node (ref "Q5") (pin "3") (pinfunction "3_3") (pintype "bidirectional"))
      (node (ref "R10") (pin "1") (pinfunction "1_1") (pintype "passive"))
      (node (ref "R11") (pin "2") (pinfunction "2_2") (pintype "passive"))
      (node (ref "R13") (pin "1") (pinfunction "1_1") (pintype "passive"))
      (node (ref "R14") (pin "1") (pinfunction "1_1") (pintype "passive"))
      (node (ref "R15") (pin "2") (pinfunction "2_2") (pintype "passive"))
      (node (ref "R16") (pin "1") (pinfunction "1_1") (pintype "passive"))
      (node (ref "R28") (pin "1") (pinfunction "1_1") (pintype "passive"))
      (node (ref "R32") (pin "2") (pinfunction "2_2") (pintype "passive"))
      (node (ref "R45") (pin "1") (pinfunction "1_1") (pintype "passive"))
      (node (ref "R46") (pin "1") (pinfunction "1_1") (pintype "passive"))
      (node (ref "R51") (pin "1") (pinfunction "1_1") (pintype "passive"))
      (node (ref "R54") (pin "1") (pinfunction "1_1") (pintype "passive"))
      (node (ref "R56") (pin "1") (pinfunction "1_1") (pintype "passive"))
      (node (ref "R58") (pin "2") (pinfunction "2_2") (pintype "passive"))
      (node (ref "R59") (pin "2") (pinfunction "2_2") (pintype "passive"))
      (node (ref "R63") (pin "2") (pinfunction "2_2") (pintype "passive"))
      (node (ref "R67") (pin "1") (pinfunction "1_1") (pintype "passive"))
      (node (ref "R9") (pin "1") (pinfunction "1_1") (pintype "passive"))
      (node (ref "REG1") (pin "3") (pinfunction "GND_3") (pintype "input"))
      (node (ref "REG1") (pin "5") (pinfunction "ON/OFF_5") (pintype "input"))
      (node (ref "REG1") (pin "6") (pinfunction "CASE_6") (pintype "input"))
      (node (ref "REG2") (pin "3") (pinfunction "GND_3") (pintype "input"))
      (node (ref "REG2") (pin "5") (pinfunction "ON/OFF_5") (pintype "input"))
      (node (ref "REG2") (pin "6") (pinfunction "CASE_6") (pintype "input"))
      (node (ref "U1") (pin "P$5-VO-") (pinfunction "-VO(5)_P$5-VO-") (pintype "bidirectional"))
      (node (ref "U1") (pin "P$6-VO-") (pinfunction "-VO(6)_P$6-VO-") (pintype "bidirectional"))
      (node (ref "U2") (pin "-") (pinfunction "4_-") (pintype "bidirectional"))
      (node (ref "U3") (pin "4") (pinfunction "GND_4") (pintype "bidirectional"))
      (node (ref "U4") (pin "11") (pinfunction "GND_11") (pintype "bidirectional"))
      (node (ref "U4") (pin "13") (pinfunction "LSS_13") (pintype "bidirectional"))
      (node (ref "X1") (pin "2") (pinfunction "2_2") (pintype "passive"))
      (node (ref "X1") (pin "3") (pinfunction "2_3") (pintype "passive"))
      (node (ref "X1") (pin "4") (pinfunction "2_4") (pintype "passive"))
      (node (ref "X1") (pin "5") (pinfunction "2_5") (pintype "passive"))
      (node (ref "X2") (pin "2") (pinfunction "2_2") (pintype "passive"))
      (node (ref "X2") (pin "3") (pinfunction "2_3") (pintype "passive"))
      (node (ref "X2") (pin "4") (pinfunction "2_4") (pintype "passive"))
      (node (ref "X2") (pin "5") (pinfunction "2_5") (pintype "passive"))
    )
    (net (code "10") (name "EN") (class "Default")
      (node (ref "R58") (pin "1") (pinfunction "1_1") (pintype "passive"))
      (node (ref "U3") (pin "5") (pinfunction "Q_5") (pintype "bidirectional"))
      (node (ref "U4") (pin "7") (pinfunction "~{EN}_7") (pintype "bidirectional"))
    )
    (net (code "11") (name "HSB") (class "Default")
      (node (ref "C16") (pin "1") (pinfunction "1_1") (pintype "bidirectional"))
      (node (ref "D3") (pin "3") (pinfunction "K_3") (pintype "passive"))
      (node (ref "DZ3") (pin "C") (pinfunction "C_C") (pintype "passive"))
      (node (ref "U4") (pin "3") (pinfunction "HSB_3") (pintype "bidirectional"))
    )
    (net (code "12") (name "HSS") (class "Default")
      (node (ref "C16") (pin "2") (pinfunction "2_2") (pintype "bidirectional"))
      (node (ref "D1") (pin "3") (pinfunction "K_3") (pintype "passive"))
      (node (ref "DZ3") (pin "A") (pinfunction "A_A") (pintype "passive"))
      (node (ref "L1") (pin "P$1") (pinfunction "1_P$1") (pintype "passive"))
      (node (ref "Q4") (pin "3") (pinfunction "3_3") (pintype "bidirectional"))
      (node (ref "Q5") (pin "1") (pinfunction "1_1") (pintype "bidirectional"))
      (node (ref "R3") (pin "2") (pinfunction "2_2") (pintype "passive"))
      (node (ref "U4") (pin "2") (pinfunction "HSS_2") (pintype "bidirectional"))
    )
    (net (code "13") (name "HVIN") (class "Default")
      (node (ref "C1") (pin "1") (pinfunction "1_1") (pintype "bidirectional"))
      (node (ref "C3") (pin "2") (pinfunction "2_2") (pintype "bidirectional"))
      (node (ref "C43") (pin "2") (pinfunction "2_2") (pintype "bidirectional"))
      (node (ref "C45") (pin "1") (pinfunction "1_1") (pintype "bidirectional"))
      (node (ref "C46") (pin "1") (pinfunction "1_1") (pintype "bidirectional"))
      (node (ref "C5") (pin "1") (pinfunction "1_1") (pintype "bidirectional"))
      (node (ref "C6") (pin "1") (pinfunction "1_1") (pintype "bidirectional"))
      (node (ref "LF2") (pin "3") (pinfunction "3_3") (pintype "bidirectional"))
      (node (ref "Q4") (pin "1") (pinfunction "1_1") (pintype "bidirectional"))
      (node (ref "R59") (pin "1") (pinfunction "1_1") (pintype "passive"))
    )
    (net (code "14") (name "Net-(C15-C2)") (class "Default")
      (node (ref "C15") (pin "2") (pinfunction "C2_2") (pintype "passive"))
      (node (ref "R3") (pin "1") (pinfunction "1_1") (pintype "passive"))
    )
    (net (code "15") (name "Net-(C25-Pad2)") (class "Default")
      (node (ref "C25") (pin "2") (pinfunction "2_2") (pintype "bidirectional"))
      (node (ref "R2") (pin "2") (pinfunction "2_2") (pintype "passive"))
    )
    (net (code "16") (name "Net-(C26-C1)") (class "Default")
      (node (ref "C20") (pin "2") (pinfunction "2_2") (pintype "bidirectional"))
      (node (ref "C22") (pin "2") (pinfunction "2_2") (pintype "bidirectional"))
      (node (ref "C24") (pin "1") (pinfunction "1_1") (pintype "bidirectional"))
      (node (ref "C25") (pin "1") (pinfunction "1_1") (pintype "bidirectional"))
      (node (ref "C26") (pin "1") (pinfunction "C1_1") (pintype "passive"))
      (node (ref "DZ2") (pin "C") (pinfunction "C_C") (pintype "passive"))
      (node (ref "LF1") (pin "4") (pinfunction "4_4") (pintype "bidirectional"))
      (node (ref "R19") (pin "2") (pinfunction "2_2") (pintype "passive"))
      (node (ref "R22") (pin "2") (pinfunction "2_2") (pintype "passive"))
      (node (ref "R23") (pin "2") (pinfunction "2_2") (pintype "passive"))
      (node (ref "U1") (pin "P$13-VIN+") (pinfunction "+VIN(13)_P$13-VIN+") (pintype "bidirectional"))
    )
    (net (code "17") (name "Net-(C29-C1)") (class "Default")
      (node (ref "C29") (pin "1") (pinfunction "C1_1") (pintype "passive"))
      (node (ref "IC2") (pin "1") (pinfunction "FB_1") (pintype "passive"))
      (node (ref "R20") (pin "1") (pinfunction "A_1") (pintype "passive"))
      (node (ref "R28") (pin "2") (pinfunction "2_2") (pintype "passive"))
    )
    (net (code "18") (name "Net-(C29-C2)") (class "Default")
      (node (ref "C29") (pin "2") (pinfunction "C2_2") (pintype "passive"))
      (node (ref "R20") (pin "2") (pinfunction "S_2") (pintype "passive"))
      (node (ref "R20") (pin "3") (pinfunction "E_3") (pintype "passive"))
      (node (ref "R24") (pin "1") (pinfunction "1_1") (pintype "passive"))
    )
    (net (code "19") (name "Net-(C32-C2)") (class "Default")
      (node (ref "C32") (pin "2") (pinfunction "C2_2") (pintype "passive"))
      (node (ref "IC4") (pin "4") (pinfunction "IN-_4") (pintype "input"))
      (node (ref "R36") (pin "2") (pinfunction "2_2") (pintype "passive"))
    )
    (net (code "20") (name "Net-(C33-C1)") (class "Default")
      (node (ref "C33") (pin "1") (pinfunction "C1_1") (pintype "passive"))
      (node (ref "IC10") (pin "3") (pinfunction "IN+_3") (pintype "input"))
      (node (ref "R37") (pin "1") (pinfunction "1_1") (pintype "passive"))
    )
    (net (code "21") (name "Net-(C34-C1)") (class "Default")
      (node (ref "C34") (pin "1") (pinfunction "C1_1") (pintype "passive"))
      (node (ref "IC10") (pin "6") (pinfunction "OUT_6") (pintype "output"))
      (node (ref "R33") (pin "1") (pinfunction "1_1") (pintype "passive"))
      (node (ref "R38") (pin "2") (pinfunction "2_2") (pintype "passive"))
    )
    (net (code "22") (name "Net-(C34-C2)") (class "Default")
      (node (ref "C34") (pin "2") (pinfunction "C2_2") (pintype "passive"))
      (node (ref "IC10") (pin "2") (pinfunction "IN-_2") (pintype "input"))
      (node (ref "R35") (pin "1") (pinfunction "1_1") (pintype "passive"))
    )
    (net (code "23") (name "Net-(C37-C1)") (class "Default")
      (node (ref "C37") (pin "1") (pinfunction "C1_1") (pintype "passive"))
      (node (ref "IC3") (pin "6") (pinfunction "OUT_6") (pintype "output"))
      (node (ref "R29") (pin "1") (pinfunction "1_1") (pintype "passive"))
      (node (ref "R39") (pin "1") (pinfunction "1_1") (pintype "passive"))
    )
    (net (code "24") (name "Net-(C37-C2)") (class "Default")
      (node (ref "C37") (pin "2") (pinfunction "C2_2") (pintype "passive"))
      (node (ref "C41") (pin "2") (pinfunction "C2_2") (pintype "passive"))
      (node (ref "IC3") (pin "2") (pinfunction "IN-_2") (pintype "input"))
      (node (ref "R41") (pin "2") (pinfunction "2_2") (pintype "passive"))
      (node (ref "R42") (pin "1") (pinfunction "1_1") (pintype "passive"))
    )
    (net (code "25") (name "Net-(C38-C1)") (class "Default")
      (node (ref "C38") (pin "1") (pinfunction "C1_1") (pintype "passive"))
      (node (ref "IC3") (pin "3") (pinfunction "IN+_3") (pintype "input"))
      (node (ref "R43") (pin "1") (pinfunction "1_1") (pintype "passive"))
    )
    (net (code "26") (name "Net-(C41-C1)") (class "Default")
      (node (ref "C41") (pin "1") (pinfunction "C1_1") (pintype "passive"))
      (node (ref "R29") (pin "2") (pinfunction "2_2") (pintype "passive"))
    )
    (net (code "27") (name "Net-(C46-Pad2)") (class "Default")
      (node (ref "C46") (pin "2") (pinfunction "2_2") (pintype "bidirectional"))
      (node (ref "R67") (pin "2") (pinfunction "2_2") (pintype "passive"))
    )
    (net (code "28") (name "Net-(C48-C1)") (class "Default")
      (node (ref "C48") (pin "1") (pinfunction "C1_1") (pintype "passive"))
      (node (ref "R47") (pin "1") (pinfunction "1_1") (pintype "passive"))
      (node (ref "R49") (pin "2") (pinfunction "2_2") (pintype "passive"))
    )
    (net (code "29") (name "Net-(C49-C2)") (class "Default")
      (node (ref "C49") (pin "2") (pinfunction "C2_2") (pintype "passive"))
      (node (ref "R48") (pin "1") (pinfunction "1_1") (pintype "passive"))
      (node (ref "R50") (pin "2") (pinfunction "2_2") (pintype "passive"))
    )
    (net (code "30") (name "Net-(C50-C1)") (class "Default")
      (node (ref "C50") (pin "1") (pinfunction "C1_1") (pintype "passive"))
      (node (ref "C53") (pin "2") (pinfunction "C2_2") (pintype "passive"))
      (node (ref "IC5") (pin "3") (pinfunction "IN+_3") (pintype "input"))
      (node (ref "R49") (pin "1") (pinfunction "1_1") (pintype "passive"))
      (node (ref "R51") (pin "2") (pinfunction "2_2") (pintype "passive"))
    )
    (net (code "31") (name "Net-(C51-C1)") (class "Default")
      (node (ref "C51") (pin "1") (pinfunction "C1_1") (pintype "passive"))
      (node (ref "C52") (pin "1") (pinfunction "C1_1") (pintype "passive"))
      (node (ref "IC5") (pin "6") (pinfunction "OUT_6") (pintype "output"))
      (node (ref "R42") (pin "2") (pinfunction "2_2") (pintype "passive"))
      (node (ref "R52") (pin "2") (pinfunction "2_2") (pintype "passive"))
    )
    (net (code "32") (name "Net-(C51-C2)") (class "Default")
      (node (ref "C51") (pin "2") (pinfunction "C2_2") (pintype "passive"))
      (node (ref "IC5") (pin "2") (pinfunction "IN-_2") (pintype "input"))
      (node (ref "R50") (pin "1") (pinfunction "1_1") (pintype "passive"))
      (node (ref "R52") (pin "1") (pinfunction "1_1") (pintype "passive"))
      (node (ref "R53") (pin "1") (pinfunction "1_1") (pintype "passive"))
    )
    (net (code "33") (name "Net-(C52-C2)") (class "Default")
      (node (ref "C52") (pin "2") (pinfunction "C2_2") (pintype "passive"))
      (node (ref "R53") (pin "2") (pinfunction "2_2") (pintype "passive"))
    )
    (net (code "34") (name "Net-(C53-C1)") (class "Default")
      (node (ref "C53") (pin "1") (pinfunction "C1_1") (pintype "passive"))
      (node (ref "R54") (pin "2") (pinfunction "2_2") (pintype "passive"))
    )
    (net (code "35") (name "Net-(C55-C1)") (class "Default")
      (node (ref "C55") (pin "1") (pinfunction "C1_1") (pintype "passive"))
      (node (ref "IC8") (pin "4") (pinfunction "IN-_4") (pintype "input"))
      (node (ref "R56") (pin "2") (pinfunction "2_2") (pintype "passive"))
      (node (ref "R57") (pin "1") (pinfunction "A_1") (pintype "passive"))
    )
    (net (code "36") (name "Net-(C55-C2)") (class "Default")
      (node (ref "C55") (pin "2") (pinfunction "C2_2") (pintype "passive"))
      (node (ref "R55") (pin "1") (pinfunction "1_1") (pintype "passive"))
      (node (ref "R57") (pin "2") (pinfunction "S_2") (pintype "passive"))
      (node (ref "R57") (pin "3") (pinfunction "E_3") (pintype "passive"))
    )
    (net (code "37") (name "Net-(C56-C2)") (class "Default")
      (node (ref "C56") (pin "2") (pinfunction "C2_2") (pintype "passive"))
      (node (ref "R68") (pin "2") (pinfunction "2_2") (pintype "passive"))
      (node (ref "U2") (pin "+") (pinfunction "3_+") (pintype "bidirectional"))
    )
    (net (code "38") (name "Net-(CT1-C_IN)") (class "Default")
      (node (ref "C10") (pin "1") (pinfunction "1_1") (pintype "passive"))
      (node (ref "C11") (pin "1") (pinfunction "1_1") (pintype "passive"))
      (node (ref "C4") (pin "1") (pinfunction "1_1") (pintype "passive"))
      (node (ref "C8") (pin "1") (pinfunction "1_1") (pintype "passive"))
      (node (ref "C9") (pin "1") (pinfunction "1_1") (pintype "passive"))
      (node (ref "CT1") (pin "1") (pinfunction "C_IN_1") (pintype "bidirectional"))
      (node (ref "R4") (pin "2") (pinfunction "2_2") (pintype "passive"))
      (node (ref "R45") (pin "2") (pinfunction "2_2") (pintype "passive"))
      (node (ref "X2") (pin "1") (pinfunction "1_1") (pintype "passive"))
    )
    (net (code "39") (name "Net-(CT1-C_OUT)") (class "Default")
      (node (ref "CT1") (pin "2") (pinfunction "C_OUT_2") (pintype "bidirectional"))
      (node (ref "L1") (pin "P$2") (pinfunction "2_P$2") (pintype "passive"))
    )
    (net (code "40") (name "Net-(DZ1-PadC)") (class "Default")
      (node (ref "DZ1") (pin "C") (pinfunction "C_C") (pintype "passive"))
      (node (ref "R25") (pin "2") (pinfunction "2_2") (pintype "passive"))
    )
    (net (code "41") (name "Net-(DZ2-PadA)") (class "Default")
      (node (ref "DZ2") (pin "A") (pinfunction "A_A") (pintype "passive"))
      (node (ref "R26") (pin "2") (pinfunction "2_2") (pintype "passive"))
      (node (ref "R27") (pin "2") (pinfunction "2_2") (pintype "passive"))
    )
    (net (code "42") (name "Net-(IC1-VI)") (class "Default")
      (node (ref "C27") (pin "1") (pinfunction "1_1") (pintype "bidirectional"))
      (node (ref "IC1") (pin "1") (pinfunction "VI_1") (pintype "input"))
      (node (ref "L4") (pin "2") (pinfunction "2_2") (pintype "passive"))
      (node (ref "R31") (pin "1") (pinfunction "1_1") (pintype "passive"))
    )
    (net (code "43") (name "Net-(IC4-IN+)") (class "Default")
      (node (ref "IC4") (pin "3") (pinfunction "IN+_3") (pintype "input"))
      (node (ref "R33") (pin "2") (pinfunction "2_2") (pintype "passive"))
      (node (ref "R34") (pin "1") (pinfunction "1_1") (pintype "passive"))
    )
    (net (code "44") (name "Net-(IC4-OUT)") (class "Default")
      (node (ref "IC4") (pin "1") (pinfunction "OUT_1") (pintype "output"))
      (node (ref "R34") (pin "2") (pinfunction "2_2") (pintype "passive"))
      (node (ref "R35") (pin "2") (pinfunction "2_2") (pintype "passive"))
    )
    (net (code "45") (name "Net-(IC8-IN+)") (class "Default")
      (node (ref "IC8") (pin "3") (pinfunction "IN+_3") (pintype "input"))
      (node (ref "R61") (pin "2") (pinfunction "S_2") (pintype "passive"))
    )
    (net (code "46") (name "Net-(IC8-OUT)") (class "Default")
      (node (ref "IC8") (pin "1") (pinfunction "OUT_1") (pintype "output"))
      (node (ref "R62") (pin "1") (pinfunction "1_1") (pintype "passive"))
    )
    (net (code "47") (name "Net-(IC9-IN+)") (class "Default")
      (node (ref "IC9") (pin "3") (pinfunction "IN+_3") (pintype "input"))
      (node (ref "R39") (pin "2") (pinfunction "2_2") (pintype "passive"))
    )
    (net (code "48") (name "Net-(IC9-IN-)") (class "Default")
      (node (ref "IC9") (pin "4") (pinfunction "IN-_4") (pintype "input"))
      (node (ref "R38") (pin "1") (pinfunction "1_1") (pintype "passive"))
    )
    (net (code "49") (name "Net-(LED1-PadC)") (class "Default")
      (node (ref "LED1") (pin "C") (pinfunction "C_C") (pintype "passive"))
      (node (ref "R65") (pin "2") (pinfunction "2_2") (pintype "passive"))
    )
    (net (code "50") (name "Net-(Q1-B)") (class "Default")
      (node (ref "Q1") (pin "1") (pinfunction "B_1") (pintype "passive"))
      (node (ref "R25") (pin "1") (pinfunction "1_1") (pintype "passive"))
    )
    (net (code "51") (name "Net-(Q1-C)") (class "Default")
      (node (ref "Q1") (pin "3") (pinfunction "C_3") (pintype "passive"))
      (node (ref "Q2") (pin "1") (pinfunction "B_1") (pintype "passive"))
      (node (ref "Q3") (pin "3") (pinfunction "C_3") (pintype "passive"))
    )
    (net (code "52") (name "Net-(Q1-E)") (class "Default")
      (node (ref "Q1") (pin "2") (pinfunction "E_2") (pintype "passive"))
      (node (ref "R22") (pin "1") (pinfunction "1_1") (pintype "passive"))
    )
    (net (code "53") (name "Net-(Q2-C)") (class "Default")
      (node (ref "Q2") (pin "3") (pinfunction "C_3") (pintype "passive"))
      (node (ref "R23") (pin "1") (pinfunction "1_1") (pintype "passive"))
      (node (ref "U1") (pin "P$11-PO") (pinfunction "PO_P$11-PO") (pintype "bidirectional"))
    )
    (net (code "54") (name "Net-(Q3-B)") (class "Default")
      (node (ref "Q3") (pin "1") (pinfunction "B_1") (pintype "passive"))
      (node (ref "R26") (pin "1") (pinfunction "1_1") (pintype "passive"))
    )
    (net (code "55") (name "Net-(Q4-Pad2)") (class "Default")
      (node (ref "Q4") (pin "2") (pinfunction "2_2") (pintype "bidirectional"))
      (node (ref "R7") (pin "2") (pinfunction "2_2") (pintype "passive"))
      (node (ref "R8") (pin "2") (pinfunction "2_2") (pintype "passive"))
    )
    (net (code "56") (name "Net-(Q5-Pad2)") (class "Default")
      (node (ref "Q5") (pin "2") (pinfunction "2_2") (pintype "bidirectional"))
      (node (ref "R5") (pin "2") (pinfunction "2_2") (pintype "passive"))
      (node (ref "R6") (pin "2") (pinfunction "2_2") (pintype "passive"))
    )
    (net (code "57") (name "Net-(R47-Pad2)") (class "Default")
      (node (ref "R47") (pin "2") (pinfunction "2_2") (pintype "passive"))
      (node (ref "X1") (pin "1") (pinfunction "1_1") (pintype "passive"))
    )
    (net (code "58") (name "Net-(R61-A)") (class "Default")
      (node (ref "R11") (pin "1") (pinfunction "1_1") (pintype "passive"))
      (node (ref "R61") (pin "1") (pinfunction "A_1") (pintype "passive"))
    )
    (net (code "59") (name "Net-(R61-E)") (class "Default")
      (node (ref "R61") (pin "3") (pinfunction "E_3") (pintype "passive"))
      (node (ref "R68") (pin "1") (pinfunction "1_1") (pintype "passive"))
    )
    (net (code "60") (name "Net-(REG1-FDBK)") (class "Default")
      (node (ref "R12") (pin "1") (pinfunction "1_1") (pintype "passive"))
      (node (ref "R13") (pin "2") (pinfunction "2_2") (pintype "passive"))
      (node (ref "REG1") (pin "4") (pinfunction "FDBK_4") (pintype "input"))
    )
    (net (code "61") (name "Net-(REG1-OUT)") (class "Default")
      (node (ref "D5") (pin "C") (pinfunction "C_C") (pintype "passive"))
      (node (ref "L3") (pin "1") (pinfunction "1_1") (pintype "passive"))
      (node (ref "REG1") (pin "2") (pinfunction "OUT_2") (pintype "output"))
    )
    (net (code "62") (name "Net-(REG1-VIN)") (class "Default")
      (node (ref "C7") (pin "1") (pinfunction "1_1") (pintype "bidirectional"))
      (node (ref "R30") (pin "1") (pinfunction "1_1") (pintype "passive"))
      (node (ref "REG1") (pin "1") (pinfunction "VIN_1") (pintype "input"))
    )
    (net (code "63") (name "Net-(REG2-FDBK)") (class "Default")
      (node (ref "R31") (pin "2") (pinfunction "2_2") (pintype "passive"))
      (node (ref "R32") (pin "1") (pinfunction "1_1") (pintype "passive"))
      (node (ref "REG2") (pin "4") (pinfunction "FDBK_4") (pintype "input"))
    )
    (net (code "64") (name "Net-(REG2-OUT)") (class "Default")
      (node (ref "D6") (pin "C") (pinfunction "C_C") (pintype "passive"))
      (node (ref "L4") (pin "1") (pinfunction "1_1") (pintype "passive"))
      (node (ref "REG2") (pin "2") (pinfunction "OUT_2") (pintype "output"))
    )
    (net (code "65") (name "Net-(REG2-VIN)") (class "Default")
      (node (ref "C18") (pin "1") (pinfunction "1_1") (pintype "bidirectional"))
      (node (ref "R21") (pin "1") (pinfunction "1_1") (pintype "passive"))
      (node (ref "REG2") (pin "1") (pinfunction "VIN_1") (pintype "input"))
    )
    (net (code "66") (name "Net-(U3-CLK)") (class "Default")
      (node (ref "R62") (pin "2") (pinfunction "2_2") (pintype "passive"))
      (node (ref "R63") (pin "1") (pinfunction "1_1") (pintype "passive"))
      (node (ref "U3") (pin "1") (pinfunction "CLK_1") (pintype "bidirectional"))
    )
    (net (code "67") (name "Net-(U3-~{CLR})") (class "Default")
      (node (ref "C58") (pin "1") (pinfunction "1_1") (pintype "bidirectional"))
      (node (ref "R64") (pin "2") (pinfunction "2_2") (pintype "passive"))
      (node (ref "U3") (pin "6") (pinfunction "~{CLR}_6") (pintype "bidirectional"))
    )
    (net (code "68") (name "Net-(U3-~{Q})") (class "Default")
      (node (ref "R65") (pin "1") (pinfunction "1_1") (pintype "passive"))
      (node (ref "U3") (pin "3") (pinfunction "~{Q}_3") (pintype "bidirectional"))
    )
    (net (code "69") (name "Net-(U4-HSGPD)") (class "Default")
      (node (ref "R8") (pin "1") (pinfunction "1_1") (pintype "passive"))
      (node (ref "U4") (pin "1") (pinfunction "HSGPD_1") (pintype "bidirectional"))
    )
    (net (code "70") (name "Net-(U4-HSGPU)") (class "Default")
      (node (ref "R7") (pin "1") (pinfunction "1_1") (pintype "passive"))
      (node (ref "U4") (pin "6") (pinfunction "HSGPU_6") (pintype "bidirectional"))
    )
    (net (code "71") (name "Net-(U4-IN)") (class "Default")
      (node (ref "R44") (pin "1") (pinfunction "1_1") (pintype "passive"))
      (node (ref "U4") (pin "8") (pinfunction "IN_8") (pintype "input"))
    )
    (net (code "72") (name "Net-(U4-LSGPD)") (class "Default")
      (node (ref "R6") (pin "1") (pinfunction "1_1") (pintype "passive"))
      (node (ref "U4") (pin "12") (pinfunction "LSGPD_12") (pintype "bidirectional"))
    )
    (net (code "73") (name "Net-(U4-LSGPU)") (class "Default")
      (node (ref "R5") (pin "1") (pinfunction "1_1") (pintype "passive"))
      (node (ref "U4") (pin "9") (pinfunction "LSGPU_9") (pintype "bidirectional"))
    )
    (net (code "74") (name "Net-(U4-RDHL)") (class "Default")
      (node (ref "R15") (pin "1") (pinfunction "1_1") (pintype "passive"))
      (node (ref "U4") (pin "16") (pinfunction "RDHL_16") (pintype "bidirectional"))
    )
    (net (code "75") (name "Net-(U4-RDLH)") (class "Default")
      (node (ref "R14") (pin "2") (pinfunction "2_2") (pintype "passive"))
      (node (ref "U4") (pin "5") (pinfunction "RDLH_5") (pintype "bidirectional"))
    )
    (net (code "76") (name "Net-(U4-VDDSYNC)") (class "Default")
      (node (ref "R17") (pin "2") (pinfunction "2_2") (pintype "passive"))
      (node (ref "U4") (pin "4") (pinfunction "VDDSYNC_4") (pintype "bidirectional"))
    )
    (net (code "77") (name "PE") (class "Default")
      (node (ref "C20") (pin "1") (pinfunction "1_1") (pintype "bidirectional"))
      (node (ref "C21") (pin "2") (pinfunction "2_2") (pintype "bidirectional"))
      (node (ref "C22") (pin "1") (pinfunction "1_1") (pintype "bidirectional"))
      (node (ref "C23") (pin "2") (pinfunction "2_2") (pintype "bidirectional"))
      (node (ref "C3") (pin "1") (pinfunction "1_1") (pintype "bidirectional"))
      (node (ref "C42") (pin "2") (pinfunction "2_2") (pintype "bidirectional"))
      (node (ref "C43") (pin "1") (pinfunction "1_1") (pintype "bidirectional"))
      (node (ref "C44") (pin "2") (pinfunction "2_2") (pintype "bidirectional"))
      (node (ref "X5") (pin "2") (pinfunction "KL_2") (pintype "passive"))
    )
    (net (code "78") (name "PIKP") (class "Default")
      (node (ref "D3") (pin "1") (pinfunction "A_1") (pintype "passive"))
      (node (ref "R17") (pin "1") (pinfunction "1_1") (pintype "passive"))
      (node (ref "R18") (pin "2") (pinfunction "2_2") (pintype "passive"))
    )
    (net (code "79") (name "PWM_IN") (class "Default")
      (node (ref "IC9") (pin "1") (pinfunction "OUT_1") (pintype "output"))
      (node (ref "R16") (pin "2") (pinfunction "2_2") (pintype "passive"))
      (node (ref "R41") (pin "1") (pinfunction "1_1") (pintype "passive"))
      (node (ref "R44") (pin "2") (pinfunction "2_2") (pintype "passive"))
    )
    (net (code "80") (name "REF25") (class "Default")
      (node (ref "C28") (pin "1") (pinfunction "1_1") (pintype "bidirectional"))
      (node (ref "IC2") (pin "2") (pinfunction "C_2") (pintype "passive"))
      (node (ref "R24") (pin "2") (pinfunction "2_2") (pintype "passive"))
      (node (ref "R36") (pin "1") (pinfunction "1_1") (pintype "passive"))
      (node (ref "R37") (pin "2") (pinfunction "2_2") (pintype "passive"))
      (node (ref "R43") (pin "2") (pinfunction "2_2") (pintype "passive"))
      (node (ref "R66") (pin "1") (pinfunction "1_1") (pintype "passive"))
    )
    (net (code "81") (name "VFBK") (class "Default")
      (node (ref "R4") (pin "1") (pinfunction "1_1") (pintype "passive"))
      (node (ref "R46") (pin "2") (pinfunction "2_2") (pintype "passive"))
      (node (ref "R48") (pin "2") (pinfunction "2_2") (pintype "passive"))
    )
    (net (code "82") (name "unconnected-(Q4-Pad4)") (class "Default")
      (node (ref "Q4") (pin "4") (pinfunction "4_4") (pintype "bidirectional"))
    )
    (net (code "83") (name "unconnected-(Q5-Pad4)") (class "Default")
      (node (ref "Q5") (pin "4") (pinfunction "4_4") (pintype "bidirectional"))
    )
    (net (code "84") (name "unconnected-(U1-+VIN(14)-PadP$14-VIN+)") (class "Default")
      (node (ref "U1") (pin "P$14-VIN+") (pinfunction "+VIN(14)_P$14-VIN+") (pintype "bidirectional"))
    )
    (net (code "85") (name "unconnected-(U1--VIN(15)-PadP$15-VIN-)") (class "Default")
      (node (ref "U1") (pin "P$15-VIN-") (pinfunction "-VIN(15)_P$15-VIN-") (pintype "bidirectional"))
    )
    (net (code "86") (name "unconnected-(U1-ALM-PadP$9-ALM)") (class "Default")
      (node (ref "U1") (pin "P$9-ALM") (pinfunction "ALM_P$9-ALM") (pintype "bidirectional"))
    )
    (net (code "87") (name "unconnected-(U1-NC(1)-PadP$1-NC)") (class "Default")
      (node (ref "U1") (pin "P$1-NC") (pinfunction "NC(1)_P$1-NC") (pintype "bidirectional"))
    )
    (net (code "88") (name "unconnected-(U1-NC(7)-PadP$7-NC)") (class "Default")
      (node (ref "U1") (pin "P$7-NC") (pinfunction "NC(7)_P$7-NC") (pintype "bidirectional"))
    )
    (net (code "89") (name "unconnected-(U1-NC(8)-PadP$8-NC)") (class "Default")
      (node (ref "U1") (pin "P$8-NC") (pinfunction "NC(8)_P$8-NC") (pintype "bidirectional"))
    )
    (net (code "90") (name "unconnected-(U1-NC(12)-PadP$12-NC)") (class "Default")
      (node (ref "U1") (pin "P$12-NC") (pinfunction "NC(12)_P$12-NC") (pintype "bidirectional"))
    )
    (net (code "91") (name "unconnected-(U1-NC(17)-PadP$17-NC)") (class "Default")
      (node (ref "U1") (pin "P$17-NC") (pinfunction "NC(17)_P$17-NC") (pintype "bidirectional"))
    )
    (net (code "92") (name "unconnected-(U1-RC-PadP$10-RC)") (class "Default")
      (node (ref "U1") (pin "P$10-RC") (pinfunction "RC_P$10-RC") (pintype "bidirectional"))
    )
    (net (code "93") (name "unconnected-(U4-LSO-Pad10)") (class "Default")
      (node (ref "U4") (pin "10") (pinfunction "LSO_10") (pintype "bidirectional"))
    )
  )
)
